# JacdacEc30xlTemplate20x20_133.net
KiCad netlist of a schematic drawn in Altium Designer
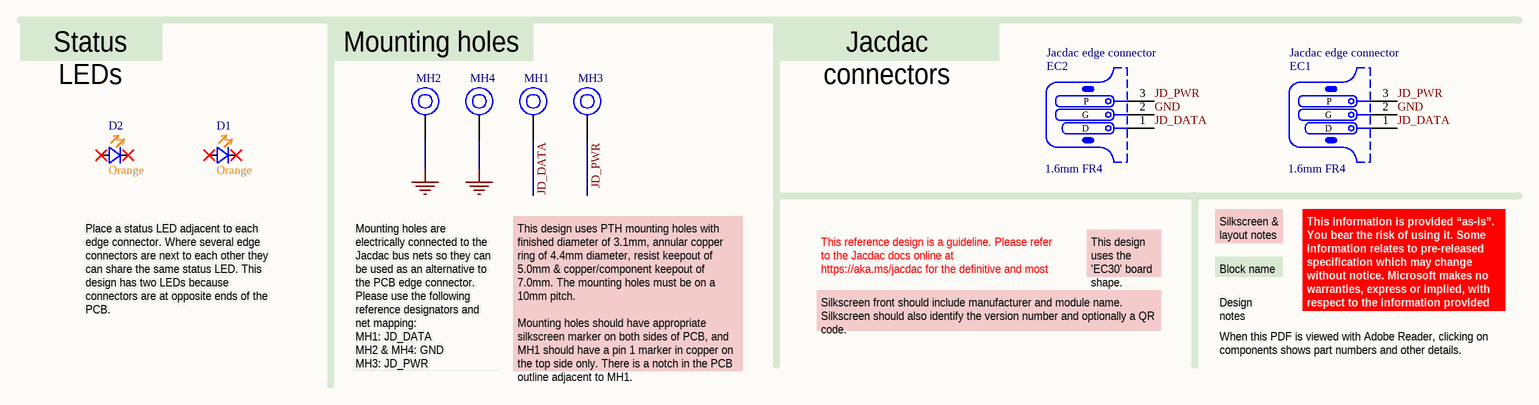
[diagram p0: JacdacEc30xlTemplate20x20 133.SchDoc]

(export (version "E")
  (design (tool "Eeschema 10.0.6"))
  (components
    (comp (ref "D1")
      (value "~")
      (footprint "0603 Orange")
      (description "LED ORANGE DIFFUSED 0603 SMD")
      (fields
        (field (name "MANUFACTURER") "Everlight Elec")
        (field (name "MANUFACTURER PART NUMBER") "19-217/S2C-AQ1R1B/3T")
        (field (name "COLOUR") "Orange")
      )
      (libsource (lib "EverlightElec") (part "19-217/S2C-AQ1R1B/3T"))
    )
    (comp (ref "D2")
      (value "~")
      (footprint "0603 Orange")
      (description "LED ORANGE DIFFUSED 0603 SMD")
      (fields
        (field (name "MANUFACTURER") "Everlight Elec")
        (field (name "MANUFACTURER PART NUMBER") "19-217/S2C-AQ1R1B/3T")
        (field (name "COLOUR") "Orange")
      )
      (libsource (lib "EverlightElec") (part "19-217/S2C-AQ1R1B/3T"))
    )
    (comp (ref "EC1")
      (value "Jacdac edge connector")
      (footprint "JACDAC_edge_connector:JACDAC_EDGE_CONNECTOR_NO_TRACES")
      (description "3 pin Jacdac edge connector 1.27mm pitch")
      (fields
        (field (name "MANUFACTURER PART NUMBER") "JACDAC_EDGE_CONNECTOR")
        (field (name "PCB TYPE") "1.6mm FR4")
        (field (name "CHECKED BY") "?")
        (field (name "CREATED BY") "D. Gakure")
      )
      (libsource (lib "generic-con") (part "Jacdac edge connector"))
    )
    (comp (ref "EC2")
      (value "Jacdac edge connector")
      (footprint "JACDAC_edge_connector:JACDAC_EDGE_CONNECTOR_NO_TRACES")
      (description "3 pin Jacdac edge connector 1.27mm pitch")
      (fields
        (field (name "MANUFACTURER PART NUMBER") "JACDAC_EDGE_CONNECTOR")
        (field (name "PCB TYPE") "1.6mm FR4")
        (field (name "CHECKED BY") "?")
        (field (name "CREATED BY") "D. Gakure")
      )
      (libsource (lib "generic-con") (part "Jacdac edge connector"))
    )
    (comp (ref "MH1")
      (value "MH_6.5MMK_4.5MMC_3.0MMD_PTH")
      (footprint "MH_6.5MMK_4.5MMC_3.0MMD_PTH")
      (description "Mounting Hole 6.5mm keepout, 4.5mm annualar ring and 3.0mm Drill PTH")
      (libsource (lib "generic") (part "MH_6.5MMK_4.5MMC_3.0MMD_PTH"))
    )
    (comp (ref "MH2")
      (value "MH_6.5MMK_4.5MMC_3.0MMD_PTH")
      (footprint "MH_6.5MMK_4.5MMC_3.0MMD_PTH")
      (description "Mounting Hole 6.5mm keepout, 4.5mm annualar ring and 3.0mm Drill PTH")
      (libsource (lib "generic") (part "MH_6.5MMK_4.5MMC_3.0MMD_PTH"))
    )
    (comp (ref "MH3")
      (value "MH_6.5MMK_4.5MMC_3.0MMD_PTH")
      (footprint "MH_6.5MMK_4.5MMC_3.0MMD_PTH")
      (description "Mounting Hole 6.5mm keepout, 4.5mm annualar ring and 3.0mm Drill PTH")
      (libsource (lib "generic") (part "MH_6.5MMK_4.5MMC_3.0MMD_PTH"))
    )
    (comp (ref "MH4")
      (value "MH_6.5MMK_4.5MMC_3.0MMD_PTH")
      (footprint "MH_6.5MMK_4.5MMC_3.0MMD_PTH")
      (description "Mounting Hole 6.5mm keepout, 4.5mm annualar ring and 3.0mm Drill PTH")
      (libsource (lib "generic") (part "MH_6.5MMK_4.5MMC_3.0MMD_PTH"))
    )
  )
  (nets
    (net (code "1") (name "/JD_DATA") (class "Default")
      (node (ref "EC1") (pin "1") (pinfunction "D_1") (pintype "passive"))
      (node (ref "EC2") (pin "1") (pinfunction "D_1") (pintype "passive"))
      (node (ref "MH1") (pin "1") (pinfunction "1_1") (pintype "passive"))
    )
    (net (code "2") (name "/JD_PWR") (class "Default")
      (node (ref "EC1") (pin "3") (pinfunction "P_3") (pintype "passive"))
      (node (ref "EC2") (pin "3") (pinfunction "P_3") (pintype "passive"))
      (node (ref "MH3") (pin "1") (pinfunction "1_1") (pintype "passive"))
    )
    (net (code "3") (name "GND") (class "Default")
      (node (ref "EC1") (pin "2") (pinfunction "G_2") (pintype "passive"))
      (node (ref "EC2") (pin "2") (pinfunction "G_2") (pintype "passive"))
      (node (ref "MH2") (pin "1") (pinfunction "1_1") (pintype "passive"))
      (node (ref "MH4") (pin "1") (pinfunction "1_1") (pintype "passive"))
    )
    (net (code "4") (name "unconnected-(D1-A-Pad2)") (class "Default")
      (node (ref "D1") (pin "2") (pinfunction "A_2") (pintype "passive+no_connect"))
    )
    (net (code "5") (name "unconnected-(D1-K-Pad1)") (class "Default")
      (node (ref "D1") (pin "1") (pinfunction "K_1") (pintype "passive+no_connect"))
    )
    (net (code "6") (name "unconnected-(D2-A-Pad2)") (class "Default")
      (node (ref "D2") (pin "2") (pinfunction "A_2") (pintype "passive+no_connect"))
    )
    (net (code "7") (name "unconnected-(D2-K-Pad1)") (class "Default")
      (node (ref "D2") (pin "1") (pinfunction "K_1") (pintype "passive+no_connect"))
    )
  )
)
